# Snickerdoodle_FPGA_JB.net
KiCad netlist of a schematic drawn in Altium Designer
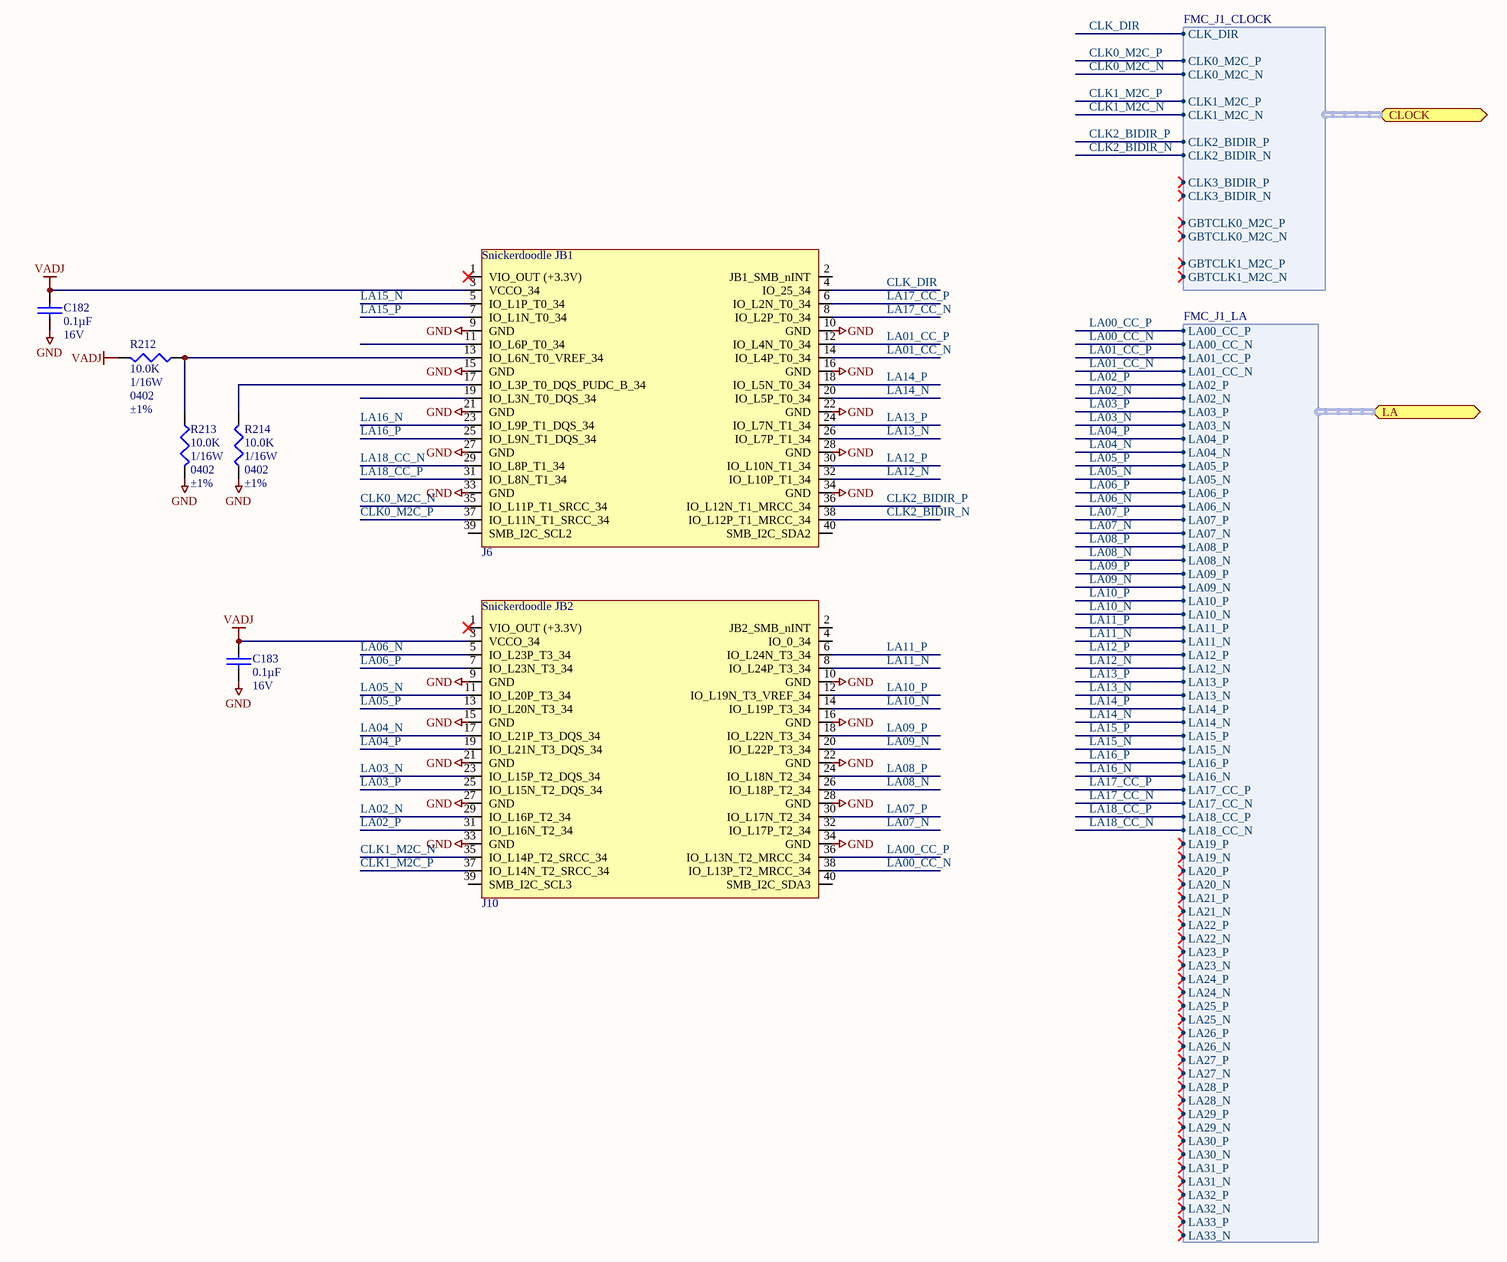
[diagram p0: Snickerdoodle FPGA JB.SchDoc]

(export (version "E")
  (design (tool "Eeschema 10.0.6"))
  (components
    (comp (ref "C182")
      (value "0.1uF")
      (footprint "C_0402")
      (description "CAP CER .10UF 16V X7R 0402")
      (fields
        (field (name "MANUFACTURER") "TDK Corporation")
        (field (name "MANUFACTURER PART NUMBER") "C1005X7R1C104K050BC")
        (field (name "CAPACITANCE") "0.1µF")
        (field (name "VOLTAGE - RATED") "16V")
      )
      (libsource (lib "Main Library") (part "C_0402_0.1UF_16V"))
    )
    (comp (ref "C183")
      (value "0.1uF")
      (footprint "C_0402")
      (description "CAP CER .10UF 16V X7R 0402")
      (fields
        (field (name "MANUFACTURER") "TDK Corporation")
        (field (name "MANUFACTURER PART NUMBER") "C1005X7R1C104K050BC")
        (field (name "CAPACITANCE") "0.1µF")
        (field (name "VOLTAGE - RATED") "16V")
      )
      (libsource (lib "Main Library") (part "C_0402_0.1UF_16V"))
    )
    (comp (ref "J6")
      (value "J_SNICKERDOODLE_JB1")
      (footprint "TFM12001-X-D-A")
      (libsource (lib "Cospan Design") (part "J_SNICKERDOODLE_JB1"))
    )
    (comp (ref "J10")
      (value "J_SNICKERDOODLE_JB2")
      (footprint "TFM12001-X-D-A")
      (libsource (lib "Cospan Design") (part "J_SNICKERDOODLE_JB2"))
    )
    (comp (ref "R212")
      (value "R_0402_10.0K")
      (footprint "R_0402")
      (description "RES 10.0K OHM 1/16W 1% 0402 SMD")
      (fields
        (field (name "MANUFACTURER") "Stackpole Electronics Inc")
        (field (name "MANUFACTURER PART NUMBER") "RMCF0402FT10K0")
        (field (name "RESISTANCE IN OHMS") "10.0K")
        (field (name "POWER (WATTS)") "1/16W")
        (field (name "CASE") "0402")
        (field (name "TOLERANCE") "±1%")
      )
      (libsource (lib "Cospan Design") (part "R_0402_10.0K"))
    )
    (comp (ref "R213")
      (value "R_0402_10.0K")
      (footprint "R_0402")
      (description "RES 10.0K OHM 1/16W 1% 0402 SMD")
      (fields
        (field (name "MANUFACTURER") "Stackpole Electronics Inc")
        (field (name "MANUFACTURER PART NUMBER") "RMCF0402FT10K0")
        (field (name "RESISTANCE IN OHMS") "10.0K")
        (field (name "POWER (WATTS)") "1/16W")
        (field (name "CASE") "0402")
        (field (name "TOLERANCE") "±1%")
      )
      (libsource (lib "Cospan Design") (part "R_0402_10.0K"))
    )
    (comp (ref "R214")
      (value "R_0402_10.0K")
      (footprint "R_0402")
      (description "RES 10.0K OHM 1/16W 1% 0402 SMD")
      (fields
        (field (name "MANUFACTURER") "Stackpole Electronics Inc")
        (field (name "MANUFACTURER PART NUMBER") "RMCF0402FT10K0")
        (field (name "RESISTANCE IN OHMS") "10.0K")
        (field (name "POWER (WATTS)") "1/16W")
        (field (name "CASE") "0402")
        (field (name "TOLERANCE") "±1%")
      )
      (libsource (lib "Cospan Design") (part "R_0402_10.0K"))
    )
  )
  (nets
    (net (code "3") (name "/CLK0_M2C_N") (class "Default")
      (node (ref "J6") (pin "35") (pinfunction "IO_L11P_T1_SRCC_34_35") (pintype "passive"))
    )
    (net (code "4") (name "/CLK0_M2C_P") (class "Default")
      (node (ref "J6") (pin "37") (pinfunction "IO_L11N_T1_SRCC_34_37") (pintype "passive"))
    )
    (net (code "5") (name "/CLK1_M2C_N") (class "Default")
      (node (ref "J10") (pin "35") (pinfunction "IO_L14P_T2_SRCC_34_35") (pintype "passive"))
    )
    (net (code "6") (name "/CLK1_M2C_P") (class "Default")
      (node (ref "J10") (pin "37") (pinfunction "IO_L14N_T2_SRCC_34_37") (pintype "passive"))
    )
    (net (code "7") (name "/CLK2_BIDIR_N") (class "Default")
      (node (ref "J6") (pin "38") (pinfunction "IO_L12P_T1_MRCC_34_38") (pintype "passive"))
    )
    (net (code "8") (name "/CLK2_BIDIR_P") (class "Default")
      (node (ref "J6") (pin "36") (pinfunction "IO_L12N_T1_MRCC_34_36") (pintype "passive"))
    )
    (net (code "9") (name "/CLK_DIR") (class "Default")
      (node (ref "J6") (pin "4") (pinfunction "IO_25_34_4") (pintype "passive"))
    )
    (net (code "10") (name "/LA00_CC_N") (class "Default")
      (node (ref "J10") (pin "38") (pinfunction "IO_L13P_T2_MRCC_34_38") (pintype "passive"))
    )
    (net (code "11") (name "/LA00_CC_P") (class "Default")
      (node (ref "J10") (pin "36") (pinfunction "IO_L13N_T2_MRCC_34_36") (pintype "passive"))
    )
    (net (code "12") (name "/LA01_CC_N") (class "Default")
      (node (ref "J6") (pin "14") (pinfunction "IO_L4P_T0_34_14") (pintype "passive"))
    )
    (net (code "13") (name "/LA01_CC_P") (class "Default")
      (node (ref "J6") (pin "12") (pinfunction "IO_L4N_T0_34_12") (pintype "passive"))
    )
    (net (code "14") (name "/LA02_N") (class "Default")
      (node (ref "J10") (pin "29") (pinfunction "IO_L16P_T2_34_29") (pintype "passive"))
    )
    (net (code "15") (name "/LA02_P") (class "Default")
      (node (ref "J10") (pin "31") (pinfunction "IO_L16N_T2_34_31") (pintype "passive"))
    )
    (net (code "16") (name "/LA03_N") (class "Default")
      (node (ref "J10") (pin "23") (pinfunction "IO_L15P_T2_DQS_34_23") (pintype "passive"))
    )
    (net (code "17") (name "/LA03_P") (class "Default")
      (node (ref "J10") (pin "25") (pinfunction "IO_L15N_T2_DQS_34_25") (pintype "passive"))
    )
    (net (code "18") (name "/LA04_N") (class "Default")
      (node (ref "J10") (pin "17") (pinfunction "IO_L21P_T3_DQS_34_17") (pintype "passive"))
    )
    (net (code "19") (name "/LA04_P") (class "Default")
      (node (ref "J10") (pin "19") (pinfunction "IO_L21N_T3_DQS_34_19") (pintype "passive"))
    )
    (net (code "20") (name "/LA05_N") (class "Default")
      (node (ref "J10") (pin "11") (pinfunction "IO_L20P_T3_34_11") (pintype "passive"))
    )
    (net (code "21") (name "/LA05_P") (class "Default")
      (node (ref "J10") (pin "13") (pinfunction "IO_L20N_T3_34_13") (pintype "passive"))
    )
    (net (code "22") (name "/LA06_N") (class "Default")
      (node (ref "J10") (pin "5") (pinfunction "IO_L23P_T3_34_5") (pintype "passive"))
    )
    (net (code "23") (name "/LA06_P") (class "Default")
      (node (ref "J10") (pin "7") (pinfunction "IO_L23N_T3_34_7") (pintype "passive"))
    )
    (net (code "24") (name "/LA07_N") (class "Default")
      (node (ref "J10") (pin "32") (pinfunction "IO_L17P_T2_34_32") (pintype "passive"))
    )
    (net (code "25") (name "/LA07_P") (class "Default")
      (node (ref "J10") (pin "30") (pinfunction "IO_L17N_T2_34_30") (pintype "passive"))
    )
    (net (code "26") (name "/LA08_N") (class "Default")
      (node (ref "J10") (pin "26") (pinfunction "IO_L18P_T2_34_26") (pintype "passive"))
    )
    (net (code "27") (name "/LA08_P") (class "Default")
      (node (ref "J10") (pin "24") (pinfunction "IO_L18N_T2_34_24") (pintype "passive"))
    )
    (net (code "28") (name "/LA09_N") (class "Default")
      (node (ref "J10") (pin "20") (pinfunction "IO_L22P_T3_34_20") (pintype "passive"))
    )
    (net (code "29") (name "/LA09_P") (class "Default")
      (node (ref "J10") (pin "18") (pinfunction "IO_L22N_T3_34_18") (pintype "passive"))
    )
    (net (code "30") (name "/LA10_N") (class "Default")
      (node (ref "J10") (pin "14") (pinfunction "IO_L19P_T3_34_14") (pintype "passive"))
    )
    (net (code "31") (name "/LA10_P") (class "Default")
      (node (ref "J10") (pin "12") (pinfunction "IO_L19N_T3_VREF_34_12") (pintype "passive"))
    )
    (net (code "32") (name "/LA11_N") (class "Default")
      (node (ref "J10") (pin "8") (pinfunction "IO_L24P_T3_34_8") (pintype "passive"))
    )
    (net (code "33") (name "/LA11_P") (class "Default")
      (node (ref "J10") (pin "6") (pinfunction "IO_L24N_T3_34_6") (pintype "passive"))
    )
    (net (code "34") (name "/LA12_N") (class "Default")
      (node (ref "J6") (pin "32") (pinfunction "IO_L10P_T1_34_32") (pintype "passive"))
    )
    (net (code "35") (name "/LA12_P") (class "Default")
      (node (ref "J6") (pin "30") (pinfunction "IO_L10N_T1_34_30") (pintype "passive"))
    )
    (net (code "36") (name "/LA13_N") (class "Default")
      (node (ref "J6") (pin "26") (pinfunction "IO_L7P_T1_34_26") (pintype "passive"))
    )
    (net (code "37") (name "/LA13_P") (class "Default")
      (node (ref "J6") (pin "24") (pinfunction "IO_L7N_T1_34_24") (pintype "passive"))
    )
    (net (code "38") (name "/LA14_N") (class "Default")
      (node (ref "J6") (pin "20") (pinfunction "IO_L5P_T0_34_20") (pintype "passive"))
    )
    (net (code "39") (name "/LA14_P") (class "Default")
      (node (ref "J6") (pin "18") (pinfunction "IO_L5N_T0_34_18") (pintype "passive"))
    )
    (net (code "40") (name "/LA15_N") (class "Default")
      (node (ref "J6") (pin "5") (pinfunction "IO_L1P_T0_34_5") (pintype "passive"))
    )
    (net (code "41") (name "/LA15_P") (class "Default")
      (node (ref "J6") (pin "7") (pinfunction "IO_L1N_T0_34_7") (pintype "passive"))
    )
    (net (code "42") (name "/LA16_N") (class "Default")
      (node (ref "J6") (pin "23") (pinfunction "IO_L9P_T1_DQS_34_23") (pintype "passive"))
    )
    (net (code "43") (name "/LA16_P") (class "Default")
      (node (ref "J6") (pin "25") (pinfunction "IO_L9N_T1_DQS_34_25") (pintype "passive"))
    )
    (net (code "44") (name "/LA17_CC_N") (class "Default")
      (node (ref "J6") (pin "8") (pinfunction "IO_L2P_T0_34_8") (pintype "passive"))
    )
    (net (code "45") (name "/LA17_CC_P") (class "Default")
      (node (ref "J6") (pin "6") (pinfunction "IO_L2N_T0_34_6") (pintype "passive"))
    )
    (net (code "46") (name "/LA18_CC_N") (class "Default")
      (node (ref "J6") (pin "29") (pinfunction "IO_L8P_T1_34_29") (pintype "passive"))
    )
    (net (code "47") (name "/LA18_CC_P") (class "Default")
      (node (ref "J6") (pin "31") (pinfunction "IO_L8N_T1_34_31") (pintype "passive"))
    )
    (net (code "50") (name "GND") (class "Default")
      (node (ref "C182") (pin "1") (pinfunction "1_1") (pintype "passive"))
      (node (ref "C183") (pin "1") (pinfunction "1_1") (pintype "passive"))
      (node (ref "J10") (pin "10") (pinfunction "GND_10") (pintype "passive"))
      (node (ref "J10") (pin "15") (pinfunction "GND_15") (pintype "passive"))
      (node (ref "J10") (pin "16") (pinfunction "GND_16") (pintype "passive"))
      (node (ref "J10") (pin "21") (pinfunction "GND_21") (pintype "passive"))
      (node (ref "J10") (pin "22") (pinfunction "GND_22") (pintype "passive"))
      (node (ref "J10") (pin "27") (pinfunction "GND_27") (pintype "passive"))
      (node (ref "J10") (pin "28") (pinfunction "GND_28") (pintype "passive"))
      (node (ref "J10") (pin "33") (pinfunction "GND_33") (pintype "passive"))
      (node (ref "J10") (pin "34") (pinfunction "GND_34") (pintype "passive"))
      (node (ref "J10") (pin "9") (pinfunction "GND_9") (pintype "passive"))
      (node (ref "J6") (pin "10") (pinfunction "GND_10") (pintype "passive"))
      (node (ref "J6") (pin "15") (pinfunction "GND_15") (pintype "passive"))
      (node (ref "J6") (pin "16") (pinfunction "GND_16") (pintype "passive"))
      (node (ref "J6") (pin "21") (pinfunction "GND_21") (pintype "passive"))
      (node (ref "J6") (pin "22") (pinfunction "GND_22") (pintype "passive"))
      (node (ref "J6") (pin "27") (pinfunction "GND_27") (pintype "passive"))
      (node (ref "J6") (pin "28") (pinfunction "GND_28") (pintype "passive"))
      (node (ref "J6") (pin "33") (pinfunction "GND_33") (pintype "passive"))
      (node (ref "J6") (pin "34") (pinfunction "GND_34") (pintype "passive"))
      (node (ref "J6") (pin "9") (pinfunction "GND_9") (pintype "passive"))
      (node (ref "R213") (pin "1") (pinfunction "1_1") (pintype "passive"))
      (node (ref "R214") (pin "2") (pinfunction "2_2") (pintype "passive"))
    )
    (net (code "51") (name "Net-(J6-IO_L3P_T0_DQS_PUDC_B_34)") (class "Default")
      (node (ref "J6") (pin "17") (pinfunction "IO_L3P_T0_DQS_PUDC_B_34_17") (pintype "passive"))
      (node (ref "R214") (pin "1") (pinfunction "1_1") (pintype "passive"))
    )
    (net (code "52") (name "Net-(J6-IO_L6N_T0_VREF_34)") (class "Default")
      (node (ref "J6") (pin "13") (pinfunction "IO_L6N_T0_VREF_34_13") (pintype "passive"))
      (node (ref "R212") (pin "2") (pinfunction "2_2") (pintype "passive"))
      (node (ref "R213") (pin "2") (pinfunction "2_2") (pintype "passive"))
    )
    (net (code "53") (name "VADJ") (class "Default")
      (node (ref "C182") (pin "2") (pinfunction "2_2") (pintype "passive"))
      (node (ref "C183") (pin "2") (pinfunction "2_2") (pintype "passive"))
      (node (ref "J10") (pin "3") (pinfunction "VCCO_34_3") (pintype "passive"))
      (node (ref "J6") (pin "3") (pinfunction "VCCO_34_3") (pintype "passive"))
      (node (ref "R212") (pin "1") (pinfunction "1_1") (pintype "passive"))
    )
    (net (code "54") (name "unconnected-(J6-IO_L3N_T0_DQS_34-Pad19)") (class "Default")
      (node (ref "J6") (pin "19") (pinfunction "IO_L3N_T0_DQS_34_19") (pintype "passive"))
    )
    (net (code "55") (name "unconnected-(J6-IO_L6P_T0_34-Pad11)") (class "Default")
      (node (ref "J6") (pin "11") (pinfunction "IO_L6P_T0_34_11") (pintype "passive"))
    )
    (net (code "56") (name "unconnected-(J6-JB1_SMB_nINT-Pad2)") (class "Default")
      (node (ref "J6") (pin "2") (pinfunction "JB1_SMB_nINT_2") (pintype "passive"))
    )
    (net (code "57") (name "unconnected-(J6-SMB_I2C_SCL2-Pad39)") (class "Default")
      (node (ref "J6") (pin "39") (pinfunction "SMB_I2C_SCL2_39") (pintype "passive"))
    )
    (net (code "58") (name "unconnected-(J6-SMB_I2C_SDA2-Pad40)") (class "Default")
      (node (ref "J6") (pin "40") (pinfunction "SMB_I2C_SDA2_40") (pintype "passive"))
    )
    (net (code "59") (name "unconnected-(J6-VIO_OUT_(+3.3V)-Pad1)") (class "Default")
      (node (ref "J6") (pin "1") (pinfunction "VIO_OUT_(+3.3V)_1") (pintype "passive+no_connect"))
    )
    (net (code "60") (name "unconnected-(J10-IO_0_34-Pad4)") (class "Default")
      (node (ref "J10") (pin "4") (pinfunction "IO_0_34_4") (pintype "passive"))
    )
    (net (code "61") (name "unconnected-(J10-JB2_SMB_nINT-Pad2)") (class "Default")
      (node (ref "J10") (pin "2") (pinfunction "JB2_SMB_nINT_2") (pintype "passive"))
    )
    (net (code "62") (name "unconnected-(J10-SMB_I2C_SCL3-Pad39)") (class "Default")
      (node (ref "J10") (pin "39") (pinfunction "SMB_I2C_SCL3_39") (pintype "passive"))
    )
    (net (code "63") (name "unconnected-(J10-SMB_I2C_SDA3-Pad40)") (class "Default")
      (node (ref "J10") (pin "40") (pinfunction "SMB_I2C_SDA3_40") (pintype "passive"))
    )
    (net (code "64") (name "unconnected-(J10-VIO_OUT_(+3.3V)-Pad1)") (class "Default")
      (node (ref "J10") (pin "1") (pinfunction "VIO_OUT_(+3.3V)_1") (pintype "passive+no_connect"))
    )
  )
)
